# board.net
KiCad netlist of a schematic drawn in EAGLE
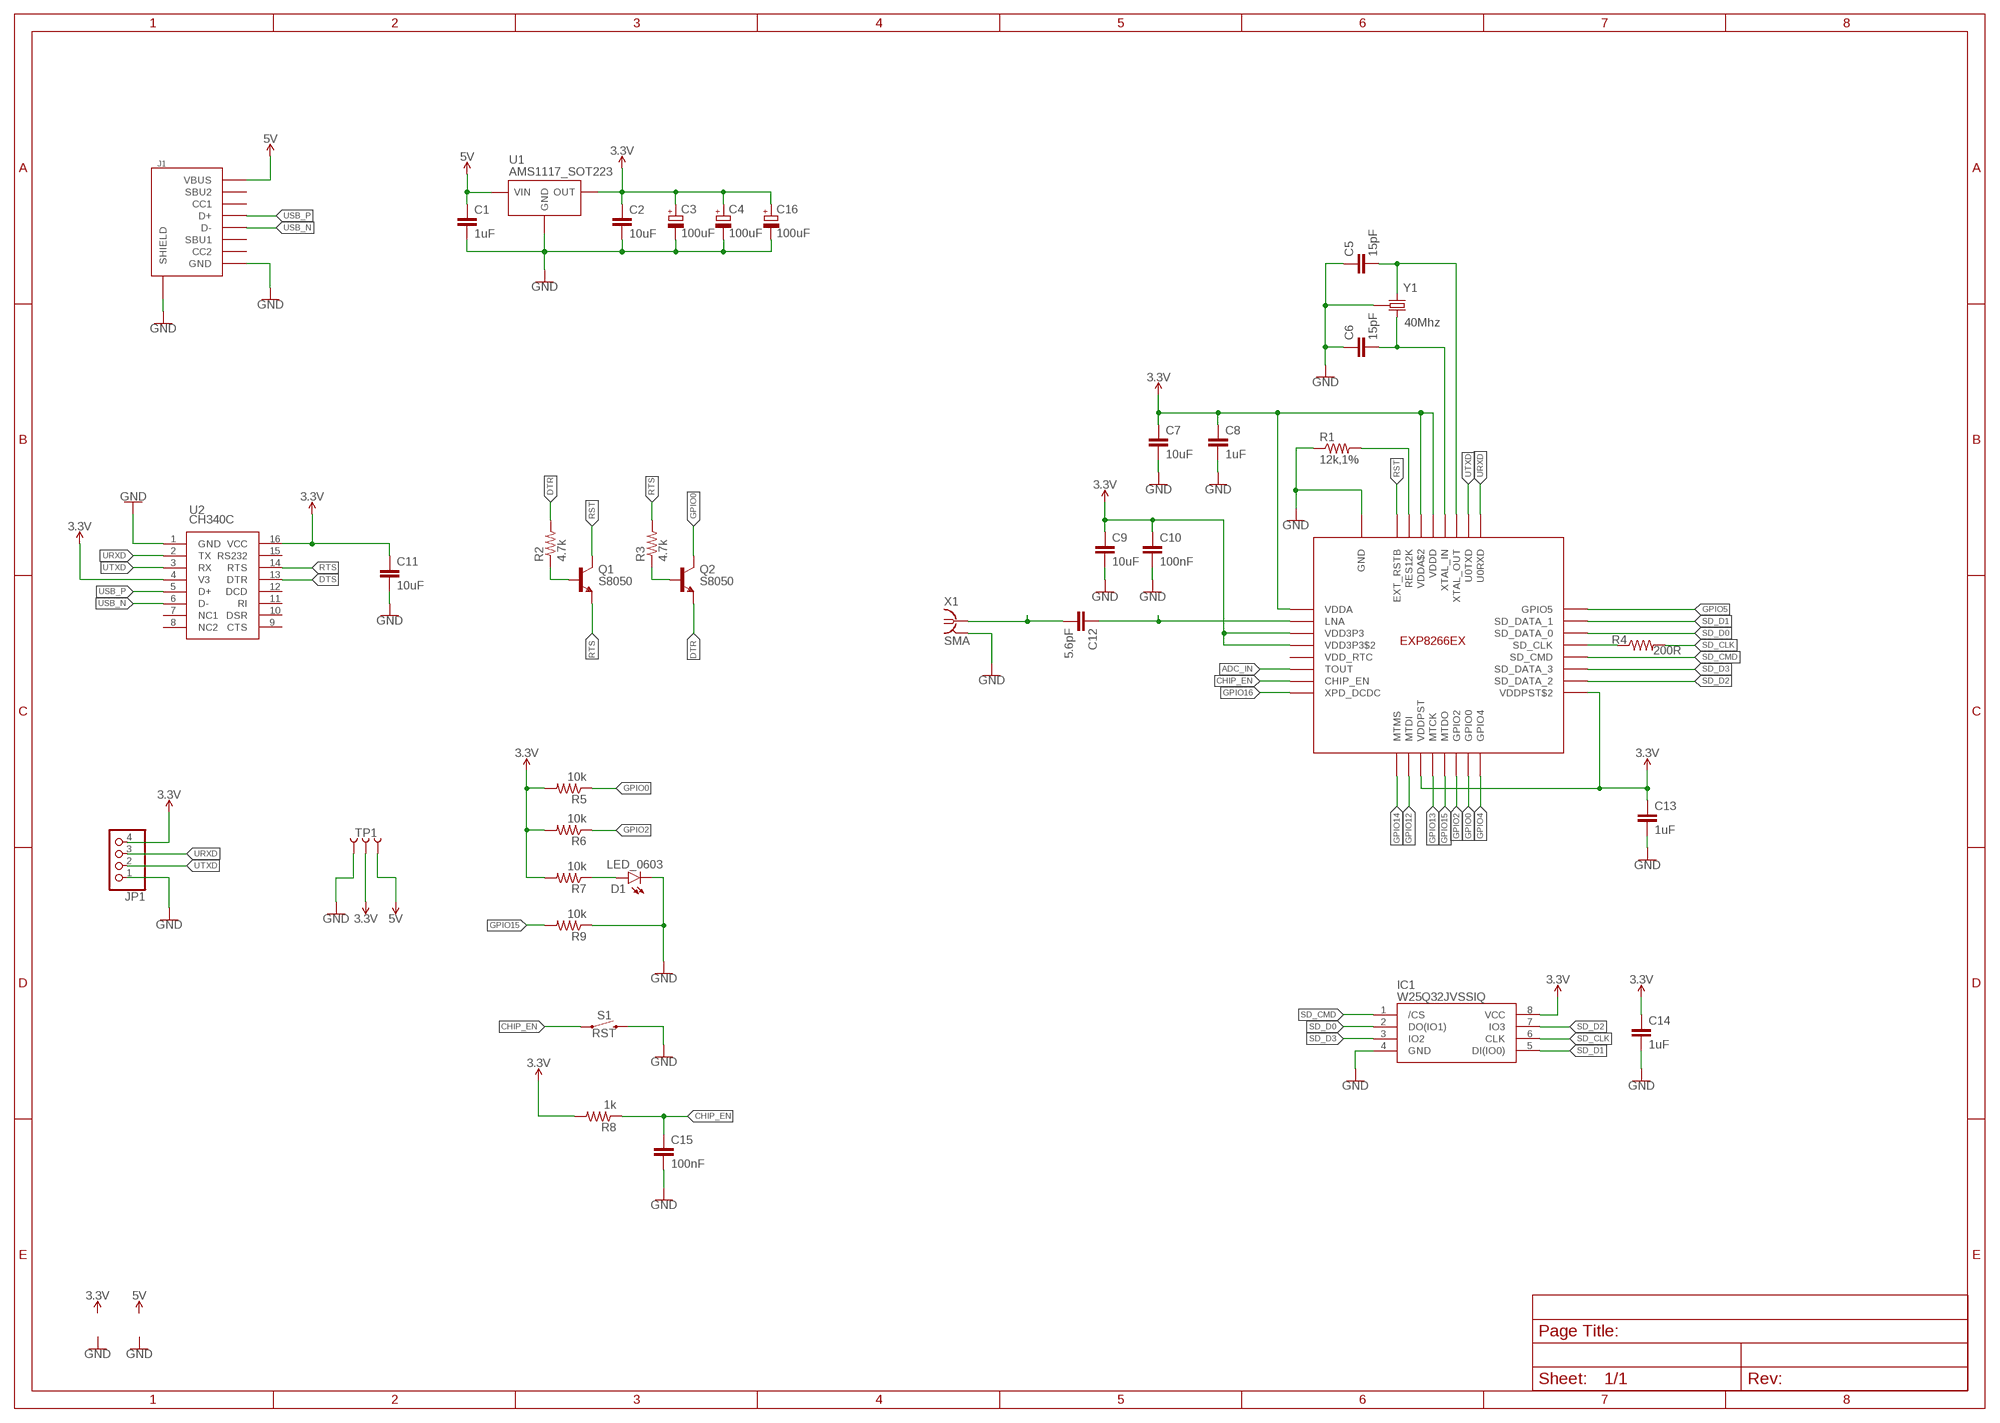
[diagram p0: schematic, sheet 1]

(export (version "E")
  (design (tool "Eeschema 10.0.6"))
  (components
    (comp (ref "C1")
      (value "1uF")
      (footprint "eagle-import:C0402")
      (libsource (lib "eagle-import") (part "C-NON-POLC0402"))
    )
    (comp (ref "C2")
      (value "10uF")
      (footprint "eagle-import:C0402")
      (libsource (lib "eagle-import") (part "C-NON-POLC0402"))
    )
    (comp (ref "C3")
      (value "100uF")
      (footprint "eagle-import:SMC_B")
      (libsource (lib "eagle-import") (part "C-POLARIZEDSMCB"))
    )
    (comp (ref "C4")
      (value "100uF")
      (footprint "eagle-import:SMC_B")
      (libsource (lib "eagle-import") (part "C-POLARIZEDSMCB"))
    )
    (comp (ref "C5")
      (value "15pF")
      (footprint "eagle-import:C0402")
      (libsource (lib "eagle-import") (part "C-NON-POLC0402"))
    )
    (comp (ref "C6")
      (value "15pF")
      (footprint "eagle-import:C0402")
      (libsource (lib "eagle-import") (part "C-NON-POLC0402"))
    )
    (comp (ref "C7")
      (value "10uF")
      (footprint "eagle-import:C0402")
      (libsource (lib "eagle-import") (part "C-NON-POLC0402"))
    )
    (comp (ref "C8")
      (value "1uF")
      (footprint "eagle-import:C0402")
      (libsource (lib "eagle-import") (part "C-NON-POLC0402"))
    )
    (comp (ref "C9")
      (value "10uF")
      (footprint "eagle-import:C0402")
      (libsource (lib "eagle-import") (part "C-NON-POLC0402"))
    )
    (comp (ref "C10")
      (value "100nF")
      (footprint "eagle-import:C0402")
      (libsource (lib "eagle-import") (part "C-NON-POLC0402"))
    )
    (comp (ref "C11")
      (value "10uF")
      (footprint "eagle-import:C0402")
      (libsource (lib "eagle-import") (part "C-NON-POLC0402"))
    )
    (comp (ref "C12")
      (value "5.6pF")
      (footprint "eagle-import:C0402")
      (libsource (lib "eagle-import") (part "C-NON-POLC0402"))
    )
    (comp (ref "C13")
      (value "1uF")
      (footprint "eagle-import:C0402")
      (libsource (lib "eagle-import") (part "C-NON-POLC0402"))
    )
    (comp (ref "C14")
      (value "1uF")
      (footprint "eagle-import:C0402")
      (libsource (lib "eagle-import") (part "C-NON-POLC0402"))
    )
    (comp (ref "C15")
      (value "100nF")
      (footprint "eagle-import:C0402")
      (libsource (lib "eagle-import") (part "C-NON-POLC0402"))
    )
    (comp (ref "C16")
      (value "100uF")
      (footprint "eagle-import:SMC_B")
      (libsource (lib "eagle-import") (part "C-POLARIZEDSMCB"))
    )
    (comp (ref "D1")
      (value "LED_0603")
      (footprint "eagle-import:LED_0603")
      (libsource (lib "eagle-import") (part "LED_0603"))
    )
    (comp (ref "IC1")
      (value "W25Q32JVSSIQ")
      (footprint "eagle-import:SOIC-8_208MIL")
      (libsource (lib "eagle-import") (part "W25Q32JVSSIQ"))
    )
    (comp (ref "J1")
      (value "USB-TYPE-C-31-M-12")
      (footprint "eagle-import:USB-TYPE-C-31-M-12")
      (libsource (lib "eagle-import") (part "USB-TYPE-C-31-M-12"))
    )
    (comp (ref "JP1")
      (value "PINHD-1X4/OCT")
      (footprint "eagle-import:1X04_OCT")
      (libsource (lib "eagle-import") (part "PINHD-1X4/OCT"))
    )
    (comp (ref "Q1")
      (value "S8050")
      (footprint "eagle-import:SOT-23-3")
      (libsource (lib "eagle-import") (part "S8050"))
    )
    (comp (ref "Q2")
      (value "S8050")
      (footprint "eagle-import:SOT-23-3")
      (libsource (lib "eagle-import") (part "S8050"))
    )
    (comp (ref "R1")
      (value "12k,1%")
      (footprint "eagle-import:R0402")
      (libsource (lib "eagle-import") (part "RR0402"))
    )
    (comp (ref "R2")
      (value "4.7k")
      (footprint "eagle-import:R0402")
      (libsource (lib "eagle-import") (part "RR0402"))
    )
    (comp (ref "R3")
      (value "4.7k")
      (footprint "eagle-import:R0402")
      (libsource (lib "eagle-import") (part "RR0402"))
    )
    (comp (ref "R4")
      (value "200R")
      (footprint "eagle-import:R0402")
      (libsource (lib "eagle-import") (part "RR0402"))
    )
    (comp (ref "R5")
      (value "10k")
      (footprint "eagle-import:R0402")
      (libsource (lib "eagle-import") (part "RR0402"))
    )
    (comp (ref "R6")
      (value "10k")
      (footprint "eagle-import:R0402")
      (libsource (lib "eagle-import") (part "RR0402"))
    )
    (comp (ref "R7")
      (value "10k")
      (footprint "eagle-import:R0402")
      (libsource (lib "eagle-import") (part "RR0402"))
    )
    (comp (ref "R8")
      (value "1k")
      (footprint "eagle-import:R0402")
      (libsource (lib "eagle-import") (part "RR0402"))
    )
    (comp (ref "R9")
      (value "10k")
      (footprint "eagle-import:R0402")
      (libsource (lib "eagle-import") (part "RR0402"))
    )
    (comp (ref "S1")
      (value "RST")
      (footprint "eagle-import:TACTILE_SWITCH_SMD_6.0X3.5MM")
      (libsource (lib "eagle-import") (part "SWITCH-SPST-SMD-6.0X3.5MM"))
    )
    (comp (ref "TP1")
      (value "TEST-POINT-3")
      (footprint "eagle-import:PAD-3X-RECT-SILK")
      (libsource (lib "eagle-import") (part "TEST-POINT-3"))
    )
    (comp (ref "U1")
      (value "AMS1117_SOT223")
      (footprint "eagle-import:SOT-223")
      (libsource (lib "eagle-import") (part "AMS1117_SOT223"))
    )
    (comp (ref "U2")
      (value "CH340C")
      (footprint "eagle-import:SOIC16")
      (libsource (lib "eagle-import") (part "CH340C"))
    )
    (comp (ref "U3")
      (value "ESP8266EX")
      (footprint "eagle-import:ESP8266EX")
      (libsource (lib "eagle-import") (part "ESP8266EX"))
    )
    (comp (ref "X1")
      (value "SMA")
      (footprint "eagle-import:SMA-END-LAUNCH-2")
      (libsource (lib "eagle-import") (part "SMA_END-LAUNCH-1"))
    )
    (comp (ref "Y1")
      (value "40Mhz")
      (footprint "eagle-import:CRYSTAL-SMD-2X2.5MM")
      (libsource (lib "eagle-import") (part "CRYSTAL-40MHZ_2520"))
    )
  )
  (nets
    (net (code "1") (name "3.3V") (class "Default")
      (node (ref "C10") (pin "1") (pinfunction "1_1") (pintype "passive"))
      (node (ref "C11") (pin "1") (pinfunction "1_1") (pintype "passive"))
      (node (ref "C13") (pin "1") (pinfunction "1_1") (pintype "passive"))
      (node (ref "C14") (pin "1") (pinfunction "1_1") (pintype "passive"))
      (node (ref "C16") (pin "+") (pinfunction "+_+") (pintype "passive"))
      (node (ref "C2") (pin "1") (pinfunction "1_1") (pintype "passive"))
      (node (ref "C3") (pin "+") (pinfunction "+_+") (pintype "passive"))
      (node (ref "C4") (pin "+") (pinfunction "+_+") (pintype "passive"))
      (node (ref "C7") (pin "1") (pinfunction "1_1") (pintype "passive"))
      (node (ref "C8") (pin "1") (pinfunction "1_1") (pintype "passive"))
      (node (ref "C9") (pin "1") (pinfunction "1_1") (pintype "passive"))
      (node (ref "IC1") (pin "8") (pinfunction "VCC_8") (pintype "bidirectional"))
      (node (ref "JP1") (pin "4") (pinfunction "4_4") (pintype "passive"))
      (node (ref "R5") (pin "2") (pinfunction "2_2") (pintype "passive"))
      (node (ref "R6") (pin "2") (pinfunction "2_2") (pintype "passive"))
      (node (ref "R7") (pin "2") (pinfunction "2_2") (pintype "passive"))
      (node (ref "R8") (pin "2") (pinfunction "2_2") (pintype "passive"))
      (node (ref "TP1") (pin "P$2") (pinfunction "2_P$2") (pintype "bidirectional"))
      (node (ref "U1") (pin "2") (pinfunction "OUT_2") (pintype "bidirectional"))
      (node (ref "U1") (pin "4") (pinfunction "OUT_4") (pintype "bidirectional"))
      (node (ref "U2") (pin "16") (pinfunction "VCC_16") (pintype "bidirectional"))
      (node (ref "U2") (pin "4") (pinfunction "V3_4") (pintype "bidirectional"))
      (node (ref "U3") (pin "VDD3P3") (pinfunction "VDD3P3_VDD3P3") (pintype "bidirectional"))
      (node (ref "U3") (pin "VDD3P3$2") (pinfunction "VDD3P3$2_VDD3P3$2") (pintype "bidirectional"))
      (node (ref "U3") (pin "VDDA") (pinfunction "VDDA_VDDA") (pintype "bidirectional"))
      (node (ref "U3") (pin "VDDA$2") (pinfunction "VDDA$2_VDDA$2") (pintype "bidirectional"))
      (node (ref "U3") (pin "VDDD") (pinfunction "VDDD_VDDD") (pintype "bidirectional"))
      (node (ref "U3") (pin "VDDPST") (pinfunction "VDDPST_VDDPST") (pintype "bidirectional"))
      (node (ref "U3") (pin "VDDPST$2") (pinfunction "VDDPST$2_VDDPST$2") (pintype "bidirectional"))
    )
    (net (code "2") (name "5V") (class "Default")
      (node (ref "C1") (pin "1") (pinfunction "1_1") (pintype "passive"))
      (node (ref "J1") (pin "VBUS1") (pinfunction "VBUS_VBUS1") (pintype "bidirectional"))
      (node (ref "J1") (pin "VBUS2") (pinfunction "VBUS_VBUS2") (pintype "bidirectional"))
      (node (ref "TP1") (pin "P$3") (pinfunction "3_P$3") (pintype "bidirectional"))
      (node (ref "U1") (pin "3") (pinfunction "VIN_3") (pintype "bidirectional"))
    )
    (net (code "3") (name "ADC_IN") (class "Default")
      (node (ref "U3") (pin "TOUT") (pinfunction "TOUT_TOUT") (pintype "bidirectional"))
    )
    (net (code "4") (name "CHIP_EN") (class "Default")
      (node (ref "C15") (pin "1") (pinfunction "1_1") (pintype "passive"))
      (node (ref "R8") (pin "1") (pinfunction "1_1") (pintype "passive"))
      (node (ref "S1") (pin "1") (pinfunction "1_1") (pintype "passive"))
      (node (ref "U3") (pin "CHIP_EN") (pinfunction "CHIP_EN_CHIP_EN") (pintype "bidirectional"))
    )
    (net (code "5") (name "DTR") (class "Default")
      (node (ref "Q2") (pin "2") (pinfunction "E_2") (pintype "passive"))
      (node (ref "R2") (pin "2") (pinfunction "2_2") (pintype "passive"))
    )
    (net (code "6") (name "DTS") (class "Default")
      (node (ref "U2") (pin "13") (pinfunction "DTR_13") (pintype "bidirectional"))
    )
    (net (code "7") (name "GND") (class "Default")
      (node (ref "C1") (pin "2") (pinfunction "2_2") (pintype "passive"))
      (node (ref "C10") (pin "2") (pinfunction "2_2") (pintype "passive"))
      (node (ref "C11") (pin "2") (pinfunction "2_2") (pintype "passive"))
      (node (ref "C13") (pin "2") (pinfunction "2_2") (pintype "passive"))
      (node (ref "C14") (pin "2") (pinfunction "2_2") (pintype "passive"))
      (node (ref "C15") (pin "2") (pinfunction "2_2") (pintype "passive"))
      (node (ref "C16") (pin "-") (pinfunction "-_-") (pintype "passive"))
      (node (ref "C2") (pin "2") (pinfunction "2_2") (pintype "passive"))
      (node (ref "C3") (pin "-") (pinfunction "-_-") (pintype "passive"))
      (node (ref "C4") (pin "-") (pinfunction "-_-") (pintype "passive"))
      (node (ref "C5") (pin "1") (pinfunction "1_1") (pintype "passive"))
      (node (ref "C6") (pin "1") (pinfunction "1_1") (pintype "passive"))
      (node (ref "C7") (pin "2") (pinfunction "2_2") (pintype "passive"))
      (node (ref "C8") (pin "2") (pinfunction "2_2") (pintype "passive"))
      (node (ref "C9") (pin "2") (pinfunction "2_2") (pintype "passive"))
      (node (ref "D1") (pin "C") (pinfunction "C_C") (pintype "passive"))
      (node (ref "IC1") (pin "4") (pinfunction "GND_4") (pintype "bidirectional"))
      (node (ref "J1") (pin "GND1") (pinfunction "GND_GND1") (pintype "bidirectional"))
      (node (ref "J1") (pin "GND2") (pinfunction "GND_GND2") (pintype "bidirectional"))
      (node (ref "J1") (pin "SHLD-B1") (pinfunction "SHIELD_SHLD-B1") (pintype "bidirectional"))
      (node (ref "J1") (pin "SHLD-B2") (pinfunction "SHIELD_SHLD-B2") (pintype "bidirectional"))
      (node (ref "J1") (pin "SHLD-B3") (pinfunction "SHIELD_SHLD-B3") (pintype "bidirectional"))
      (node (ref "J1") (pin "SHLD-B4") (pinfunction "SHIELD_SHLD-B4") (pintype "bidirectional"))
      (node (ref "J1") (pin "SHLD-T1") (pinfunction "SHIELD_SHLD-T1") (pintype "bidirectional"))
      (node (ref "J1") (pin "SHLD-T2") (pinfunction "SHIELD_SHLD-T2") (pintype "bidirectional"))
      (node (ref "J1") (pin "SHLD-T3") (pinfunction "SHIELD_SHLD-T3") (pintype "bidirectional"))
      (node (ref "J1") (pin "SHLD-T4") (pinfunction "SHIELD_SHLD-T4") (pintype "bidirectional"))
      (node (ref "JP1") (pin "1") (pinfunction "1_1") (pintype "passive"))
      (node (ref "R1") (pin "1") (pinfunction "1_1") (pintype "passive"))
      (node (ref "R9") (pin "1") (pinfunction "1_1") (pintype "passive"))
      (node (ref "S1") (pin "2") (pinfunction "2_2") (pintype "passive"))
      (node (ref "TP1") (pin "P$1") (pinfunction "1_P$1") (pintype "bidirectional"))
      (node (ref "U1") (pin "1") (pinfunction "GND_1") (pintype "bidirectional"))
      (node (ref "U2") (pin "1") (pinfunction "GND_1") (pintype "bidirectional"))
      (node (ref "U3") (pin "GND") (pinfunction "GND_GND") (pintype "bidirectional"))
      (node (ref "X1") (pin "G@1") (pinfunction "2_G@1") (pintype "passive"))
      (node (ref "X1") (pin "G@2") (pinfunction "2_G@2") (pintype "passive"))
      (node (ref "X1") (pin "G@3") (pinfunction "2_G@3") (pintype "passive"))
      (node (ref "X1") (pin "G@4") (pinfunction "2_G@4") (pintype "passive"))
      (node (ref "Y1") (pin "P2") (pinfunction "GND_P2") (pintype "power_in"))
      (node (ref "Y1") (pin "P4") (pinfunction "GND_P4") (pintype "power_in"))
    )
    (net (code "8") (name "GPIO0") (class "Default")
      (node (ref "Q2") (pin "3") (pinfunction "C_3") (pintype "passive"))
      (node (ref "R5") (pin "1") (pinfunction "1_1") (pintype "passive"))
      (node (ref "U3") (pin "GPIO0") (pinfunction "GPIO0_GPIO0") (pintype "bidirectional"))
    )
    (net (code "9") (name "GPIO2") (class "Default")
      (node (ref "R6") (pin "1") (pinfunction "1_1") (pintype "passive"))
      (node (ref "U3") (pin "GPIO2") (pinfunction "GPIO2_GPIO2") (pintype "bidirectional"))
    )
    (net (code "10") (name "GPIO4") (class "Default")
      (node (ref "U3") (pin "GPIO4") (pinfunction "GPIO4_GPIO4") (pintype "bidirectional"))
    )
    (net (code "11") (name "GPIO5") (class "Default")
      (node (ref "U3") (pin "GPOIO5") (pinfunction "GPIO5_GPOIO5") (pintype "bidirectional"))
    )
    (net (code "12") (name "GPIO12") (class "Default")
      (node (ref "U3") (pin "MTDI") (pinfunction "MTDI_MTDI") (pintype "bidirectional"))
    )
    (net (code "13") (name "GPIO13") (class "Default")
      (node (ref "U3") (pin "MTCK") (pinfunction "MTCK_MTCK") (pintype "bidirectional"))
    )
    (net (code "14") (name "GPIO14") (class "Default")
      (node (ref "U3") (pin "MTMS") (pinfunction "MTMS_MTMS") (pintype "bidirectional"))
    )
    (net (code "15") (name "GPIO15") (class "Default")
      (node (ref "R9") (pin "2") (pinfunction "2_2") (pintype "passive"))
      (node (ref "U3") (pin "MTDO") (pinfunction "MTDO_MTDO") (pintype "bidirectional"))
    )
    (net (code "16") (name "GPIO16") (class "Default")
      (node (ref "U3") (pin "XPD_DCDC") (pinfunction "XPD_DCDC_XPD_DCDC") (pintype "bidirectional"))
    )
    (net (code "17") (name "Net-(C12-Pad1)") (class "Default")
      (node (ref "C12") (pin "1") (pinfunction "1_1") (pintype "passive"))
      (node (ref "U3") (pin "LNA") (pinfunction "LNA_LNA") (pintype "bidirectional"))
    )
    (net (code "18") (name "Net-(C12-Pad2)") (class "Default")
      (node (ref "C12") (pin "2") (pinfunction "2_2") (pintype "passive"))
      (node (ref "X1") (pin "1") (pinfunction "1_1") (pintype "passive"))
    )
    (net (code "19") (name "Net-(D1-PadA)") (class "Default")
      (node (ref "D1") (pin "A") (pinfunction "A_A") (pintype "passive"))
      (node (ref "R7") (pin "1") (pinfunction "1_1") (pintype "passive"))
    )
    (net (code "20") (name "Net-(Q1-B)") (class "Default")
      (node (ref "Q1") (pin "1") (pinfunction "B_1") (pintype "passive"))
      (node (ref "R2") (pin "1") (pinfunction "1_1") (pintype "passive"))
    )
    (net (code "21") (name "Net-(Q2-B)") (class "Default")
      (node (ref "Q2") (pin "1") (pinfunction "B_1") (pintype "passive"))
      (node (ref "R3") (pin "1") (pinfunction "1_1") (pintype "passive"))
    )
    (net (code "22") (name "Net-(R1-Pad2)") (class "Default")
      (node (ref "R1") (pin "2") (pinfunction "2_2") (pintype "passive"))
      (node (ref "U3") (pin "RES12K") (pinfunction "RES12K_RES12K") (pintype "bidirectional"))
    )
    (net (code "23") (name "Net-(R4-Pad1)") (class "Default")
      (node (ref "R4") (pin "1") (pinfunction "1_1") (pintype "passive"))
      (node (ref "U3") (pin "SD_CLK") (pinfunction "SD_CLK_SD_CLK") (pintype "bidirectional"))
    )
    (net (code "24") (name "Net-(Y1-1)") (class "Default")
      (node (ref "C5") (pin "2") (pinfunction "2_2") (pintype "passive"))
      (node (ref "U3") (pin "XTAL_OUT") (pinfunction "XTAL_OUT_XTAL_OUT") (pintype "bidirectional"))
      (node (ref "Y1") (pin "P1") (pinfunction "1_P1") (pintype "passive"))
    )
    (net (code "25") (name "Net-(Y1-2)") (class "Default")
      (node (ref "C6") (pin "2") (pinfunction "2_2") (pintype "passive"))
      (node (ref "U3") (pin "XTAL_IN") (pinfunction "XTAL_IN_XTAL_IN") (pintype "bidirectional"))
      (node (ref "Y1") (pin "P3") (pinfunction "2_P3") (pintype "passive"))
    )
    (net (code "26") (name "RST") (class "Default")
      (node (ref "Q1") (pin "3") (pinfunction "C_3") (pintype "passive"))
      (node (ref "U3") (pin "EXT_RSTB") (pinfunction "EXT_RSTB_EXT_RSTB") (pintype "bidirectional"))
    )
    (net (code "27") (name "RTS") (class "Default")
      (node (ref "Q1") (pin "2") (pinfunction "E_2") (pintype "passive"))
      (node (ref "R3") (pin "2") (pinfunction "2_2") (pintype "passive"))
      (node (ref "U2") (pin "14") (pinfunction "RTS_14") (pintype "bidirectional"))
    )
    (net (code "28") (name "SD_CLK") (class "Default")
      (node (ref "IC1") (pin "6") (pinfunction "CLK_6") (pintype "bidirectional"))
      (node (ref "R4") (pin "2") (pinfunction "2_2") (pintype "passive"))
    )
    (net (code "29") (name "SD_CMD") (class "Default")
      (node (ref "IC1") (pin "1") (pinfunction "/CS_1") (pintype "bidirectional"))
      (node (ref "U3") (pin "SD_CMD") (pinfunction "SD_CMD_SD_CMD") (pintype "bidirectional"))
    )
    (net (code "30") (name "SD_D0") (class "Default")
      (node (ref "IC1") (pin "2") (pinfunction "DO(IO1)_2") (pintype "bidirectional"))
      (node (ref "U3") (pin "SD_DATA_0") (pinfunction "SD_DATA_0_SD_DATA_0") (pintype "bidirectional"))
    )
    (net (code "31") (name "SD_D1") (class "Default")
      (node (ref "IC1") (pin "5") (pinfunction "DI(IO0)_5") (pintype "bidirectional"))
      (node (ref "U3") (pin "SD_DATA_1") (pinfunction "SD_DATA_1_SD_DATA_1") (pintype "bidirectional"))
    )
    (net (code "32") (name "SD_D2") (class "Default")
      (node (ref "IC1") (pin "7") (pinfunction "IO3_7") (pintype "bidirectional"))
      (node (ref "U3") (pin "SD_DATA_2") (pinfunction "SD_DATA_2_SD_DATA_2") (pintype "bidirectional"))
    )
    (net (code "33") (name "SD_D3") (class "Default")
      (node (ref "IC1") (pin "3") (pinfunction "IO2_3") (pintype "bidirectional"))
      (node (ref "U3") (pin "SD_DATA_3") (pinfunction "SD_DATA_3_SD_DATA_3") (pintype "bidirectional"))
    )
    (net (code "34") (name "URXD") (class "Default")
      (node (ref "JP1") (pin "3") (pinfunction "3_3") (pintype "passive"))
      (node (ref "U2") (pin "2") (pinfunction "TX_2") (pintype "bidirectional"))
      (node (ref "U3") (pin "U0RXD") (pinfunction "U0RXD_U0RXD") (pintype "bidirectional"))
    )
    (net (code "35") (name "USB_N") (class "Default")
      (node (ref "J1") (pin "A7") (pinfunction "D-_A7") (pintype "bidirectional"))
      (node (ref "J1") (pin "B7") (pinfunction "D-_B7") (pintype "bidirectional"))
      (node (ref "U2") (pin "6") (pinfunction "D-_6") (pintype "bidirectional"))
    )
    (net (code "36") (name "USB_P") (class "Default")
      (node (ref "J1") (pin "A6") (pinfunction "D+_A6") (pintype "bidirectional"))
      (node (ref "J1") (pin "B6") (pinfunction "D+_B6") (pintype "bidirectional"))
      (node (ref "U2") (pin "5") (pinfunction "D+_5") (pintype "bidirectional"))
    )
    (net (code "37") (name "UTXD") (class "Default")
      (node (ref "JP1") (pin "2") (pinfunction "2_2") (pintype "passive"))
      (node (ref "U2") (pin "3") (pinfunction "RX_3") (pintype "bidirectional"))
      (node (ref "U3") (pin "U0TXD") (pinfunction "U0TXD_U0TXD") (pintype "bidirectional"))
    )
    (net (code "38") (name "unconnected-(J1-CC1-PadA5)") (class "Default")
      (node (ref "J1") (pin "A5") (pinfunction "CC1_A5") (pintype "bidirectional"))
    )
    (net (code "39") (name "unconnected-(J1-CC2-PadB5)") (class "Default")
      (node (ref "J1") (pin "B5") (pinfunction "CC2_B5") (pintype "bidirectional"))
    )
    (net (code "40") (name "unconnected-(J1-SBU1-PadA8)") (class "Default")
      (node (ref "J1") (pin "A8") (pinfunction "SBU1_A8") (pintype "bidirectional"))
    )
    (net (code "41") (name "unconnected-(J1-SBU2-PadB8)") (class "Default")
      (node (ref "J1") (pin "B8") (pinfunction "SBU2_B8") (pintype "bidirectional"))
    )
    (net (code "42") (name "unconnected-(U2-CTS-Pad9)") (class "Default")
      (node (ref "U2") (pin "9") (pinfunction "CTS_9") (pintype "bidirectional"))
    )
    (net (code "43") (name "unconnected-(U2-DCD-Pad12)") (class "Default")
      (node (ref "U2") (pin "12") (pinfunction "DCD_12") (pintype "bidirectional"))
    )
    (net (code "44") (name "unconnected-(U2-DSR-Pad10)") (class "Default")
      (node (ref "U2") (pin "10") (pinfunction "DSR_10") (pintype "bidirectional"))
    )
    (net (code "45") (name "unconnected-(U2-NC1-Pad7)") (class "Default")
      (node (ref "U2") (pin "7") (pinfunction "NC1_7") (pintype "bidirectional"))
    )
    (net (code "46") (name "unconnected-(U2-NC2-Pad8)") (class "Default")
      (node (ref "U2") (pin "8") (pinfunction "NC2_8") (pintype "bidirectional"))
    )
    (net (code "47") (name "unconnected-(U2-RI-Pad11)") (class "Default")
      (node (ref "U2") (pin "11") (pinfunction "RI_11") (pintype "bidirectional"))
    )
    (net (code "48") (name "unconnected-(U2-RS232-Pad15)") (class "Default")
      (node (ref "U2") (pin "15") (pinfunction "RS232_15") (pintype "bidirectional"))
    )
    (net (code "49") (name "unconnected-(U3-PadVDD_RTC)") (class "Default")
      (node (ref "U3") (pin "VDD_RTC") (pinfunction "VDD_RTC_VDD_RTC") (pintype "bidirectional"))
    )
  )
)
